# control_board_v006_Rev6.net
KiCad netlist of a schematic drawn in EAGLE
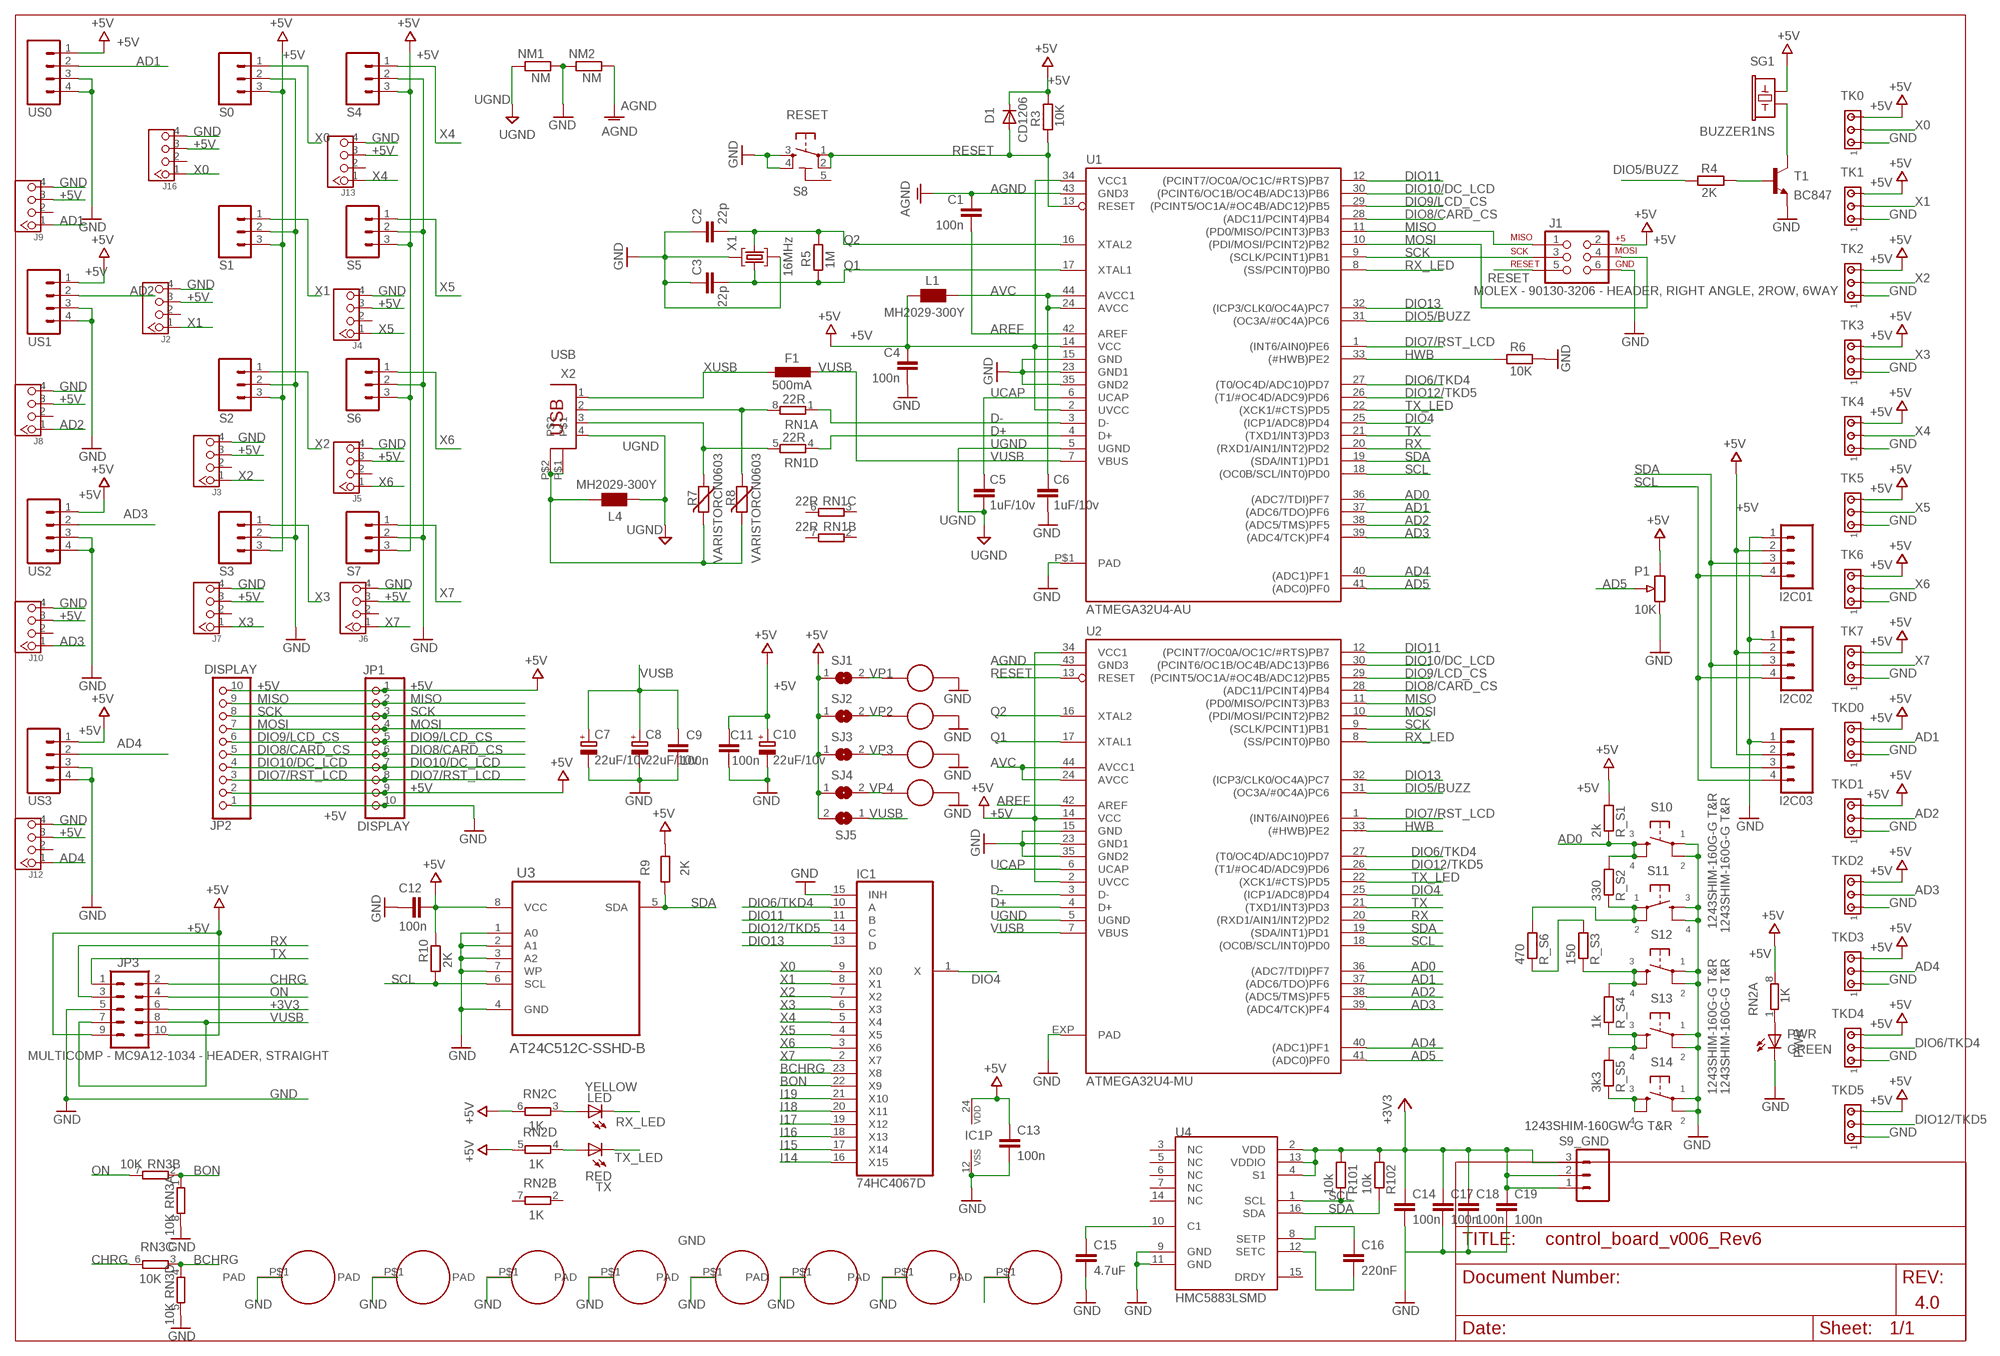
[diagram p0: schematic, sheet 1]

(export (version "E")
  (design (tool "Eeschema 10.0.6"))
  (components
    (comp (ref "C1")
      (value "100n")
      (footprint "eagle-import:C0603-ROUND")
      (libsource (lib "eagle-import") (part "C-EUC0603"))
    )
    (comp (ref "C2")
      (value "22p")
      (footprint "eagle-import:C0603-ROUND")
      (libsource (lib "eagle-import") (part "C-EUC0603"))
    )
    (comp (ref "C3")
      (value "22p")
      (footprint "eagle-import:C0603-ROUND")
      (libsource (lib "eagle-import") (part "C-EUC0603"))
    )
    (comp (ref "C4")
      (value "100n")
      (footprint "eagle-import:C0603-ROUND")
      (libsource (lib "eagle-import") (part "C-EUC0603"))
    )
    (comp (ref "C5")
      (value "1uF/10v")
      (footprint "eagle-import:C0603-ROUND")
      (libsource (lib "eagle-import") (part "C-EUC0603"))
    )
    (comp (ref "C6")
      (value "1uF/10v")
      (footprint "eagle-import:C0603-ROUND")
      (libsource (lib "eagle-import") (part "C-EUC0603"))
    )
    (comp (ref "C7")
      (value "22uF/10v")
      (footprint "eagle-import:SMC_B")
      (libsource (lib "eagle-import") (part "CPOL-EUSMCB"))
    )
    (comp (ref "C8")
      (value "22uF/10v")
      (footprint "eagle-import:SMC_B")
      (libsource (lib "eagle-import") (part "CPOL-EUSMCB"))
    )
    (comp (ref "C9")
      (value "100n")
      (footprint "eagle-import:C0603-ROUND")
      (libsource (lib "eagle-import") (part "C-EUC0603"))
    )
    (comp (ref "C10")
      (value "22uF/10v")
      (footprint "eagle-import:SMC_B")
      (libsource (lib "eagle-import") (part "CPOL-EUSMCB"))
    )
    (comp (ref "C11")
      (value "100n")
      (footprint "eagle-import:C0603-ROUND")
      (libsource (lib "eagle-import") (part "C-EUC0603"))
    )
    (comp (ref "C12")
      (value "100n")
      (footprint "eagle-import:C0603-ROUND")
      (libsource (lib "eagle-import") (part "C-EUC0603"))
    )
    (comp (ref "C13")
      (value "100n")
      (footprint "eagle-import:C0603-ROUND")
      (libsource (lib "eagle-import") (part "C-EUC0603"))
    )
    (comp (ref "C14")
      (value "100n")
      (footprint "eagle-import:C0603-ROUND")
      (libsource (lib "eagle-import") (part "C-EUC0603"))
    )
    (comp (ref "C15")
      (value "4.7uF")
      (footprint "eagle-import:C0603-ROUND")
      (libsource (lib "eagle-import") (part "C-EUC0603"))
    )
    (comp (ref "C16")
      (value "220nF")
      (footprint "eagle-import:C0603-ROUND")
      (libsource (lib "eagle-import") (part "C-EUC0603"))
    )
    (comp (ref "C17")
      (value "100n")
      (footprint "eagle-import:C0603-ROUND")
      (libsource (lib "eagle-import") (part "C-EUC0603"))
    )
    (comp (ref "C18")
      (value "100n")
      (footprint "eagle-import:C0603-ROUND")
      (libsource (lib "eagle-import") (part "C-EUC0603"))
    )
    (comp (ref "C19")
      (value "100n")
      (footprint "eagle-import:C0603-ROUND")
      (libsource (lib "eagle-import") (part "C-EUC0603"))
    )
    (comp (ref "D1")
      (value "CD1206")
      (footprint "eagle-import:MINIMELF")
      (libsource (lib "eagle-import") (part "DIODE-MINIMELF"))
    )
    (comp (ref "F1")
      (value "500mA")
      (footprint "eagle-import:L1812")
      (libsource (lib "eagle-import") (part "L-EUL1812"))
    )
    (comp (ref "H1")
      (value "2.5-MOUNTING-HOLE")
      (footprint "eagle-import:2.5PAD")
      (libsource (lib "eagle-import") (part "2.5-MOUNTING-HOLE"))
    )
    (comp (ref "H2")
      (value "2.5-MOUNTING-HOLE")
      (footprint "eagle-import:2.5PAD")
      (libsource (lib "eagle-import") (part "2.5-MOUNTING-HOLE"))
    )
    (comp (ref "H3")
      (value "2.5-MOUNTING-HOLE")
      (footprint "eagle-import:2.5PAD")
      (libsource (lib "eagle-import") (part "2.5-MOUNTING-HOLE"))
    )
    (comp (ref "H4")
      (value "2.5-MOUNTING-HOLE")
      (footprint "eagle-import:2.5PAD")
      (libsource (lib "eagle-import") (part "2.5-MOUNTING-HOLE"))
    )
    (comp (ref "H5")
      (value "2.5-MOUNTING-HOLE")
      (footprint "eagle-import:2.5PAD")
      (libsource (lib "eagle-import") (part "2.5-MOUNTING-HOLE"))
    )
    (comp (ref "H6")
      (value "2.5-MOUNTING-HOLE")
      (footprint "eagle-import:2.5PAD")
      (libsource (lib "eagle-import") (part "2.5-MOUNTING-HOLE"))
    )
    (comp (ref "H7")
      (value "2.5-MOUNTING-HOLE")
      (footprint "eagle-import:2.5PAD")
      (libsource (lib "eagle-import") (part "2.5-MOUNTING-HOLE"))
    )
    (comp (ref "H8")
      (value "2.5-MOUNTING-HOLE")
      (footprint "eagle-import:2.5PAD")
      (libsource (lib "eagle-import") (part "2.5-MOUNTING-HOLE"))
    )
    (comp (ref "I2C01")
      (value "M04PTH")
      (footprint "eagle-import:1X04")
      (libsource (lib "eagle-import") (part "M04PTH"))
    )
    (comp (ref "I2C02")
      (value "M04PTH")
      (footprint "eagle-import:1X04")
      (libsource (lib "eagle-import") (part "M04PTH"))
    )
    (comp (ref "I2C03")
      (value "M04PTH")
      (footprint "eagle-import:1X04")
      (libsource (lib "eagle-import") (part "M04PTH"))
    )
    (comp (ref "IC1")
      (value "74HC4067D")
      (footprint "eagle-import:SO24W")
      (libsource (lib "eagle-import") (part "4067D"))
    )
    (comp (ref "J1")
      (value "MOLEX - 90130-3206 - HEADER, RIGHT ANGLE, 2ROW, 6WAY")
      (footprint "eagle-import:2X3")
      (libsource (lib "eagle-import") (part "AVR_SPI_PRG_6PTH"))
    )
    (comp (ref "J2")
      (value "TWIG-4P-2.0-2.0")
      (footprint "eagle-import:4P-2.0")
      (libsource (lib "eagle-import") (part "TWIG-4P-2.0-2.0"))
    )
    (comp (ref "J3")
      (value "TWIG-4P-2.0-2.0")
      (footprint "eagle-import:4P-2.0")
      (libsource (lib "eagle-import") (part "TWIG-4P-2.0-2.0"))
    )
    (comp (ref "J4")
      (value "TWIG-4P-2.0-2.0")
      (footprint "eagle-import:4P-2.0")
      (libsource (lib "eagle-import") (part "TWIG-4P-2.0-2.0"))
    )
    (comp (ref "J5")
      (value "TWIG-4P-2.0-2.0")
      (footprint "eagle-import:4P-2.0")
      (libsource (lib "eagle-import") (part "TWIG-4P-2.0-2.0"))
    )
    (comp (ref "J6")
      (value "TWIG-4P-2.0-2.0")
      (footprint "eagle-import:4P-2.0")
      (libsource (lib "eagle-import") (part "TWIG-4P-2.0-2.0"))
    )
    (comp (ref "J7")
      (value "TWIG-4P-2.0-2.0")
      (footprint "eagle-import:4P-2.0")
      (libsource (lib "eagle-import") (part "TWIG-4P-2.0-2.0"))
    )
    (comp (ref "J8")
      (value "TWIG-4P-2.0-2.0")
      (footprint "eagle-import:4P-2.0")
      (libsource (lib "eagle-import") (part "TWIG-4P-2.0-2.0"))
    )
    (comp (ref "J9")
      (value "TWIG-4P-2.0-2.0")
      (footprint "eagle-import:4P-2.0")
      (libsource (lib "eagle-import") (part "TWIG-4P-2.0-2.0"))
    )
    (comp (ref "J10")
      (value "TWIG-4P-2.0-2.0")
      (footprint "eagle-import:4P-2.0")
      (libsource (lib "eagle-import") (part "TWIG-4P-2.0-2.0"))
    )
    (comp (ref "J12")
      (value "TWIG-4P-2.0-2.0")
      (footprint "eagle-import:4P-2.0")
      (libsource (lib "eagle-import") (part "TWIG-4P-2.0-2.0"))
    )
    (comp (ref "J13")
      (value "TWIG-4P-2.0-2.0")
      (footprint "eagle-import:4P-2.0")
      (libsource (lib "eagle-import") (part "TWIG-4P-2.0-2.0"))
    )
    (comp (ref "J16")
      (value "TWIG-4P-2.0-2.0")
      (footprint "eagle-import:4P-2.0")
      (libsource (lib "eagle-import") (part "TWIG-4P-2.0-2.0"))
    )
    (comp (ref "JP1")
      (value "DISPLAY")
      (footprint "eagle-import:1X10-TH")
      (libsource (lib "eagle-import") (part "PINHD-1X10TH"))
    )
    (comp (ref "JP2")
      (value "DISPLAY")
      (footprint "eagle-import:1X10-TH")
      (libsource (lib "eagle-import") (part "PINHD-1X10TH"))
    )
    (comp (ref "JP3")
      (value "MULTICOMP - MC9A12-1034 - HEADER, STRAIGHT")
      (footprint "eagle-import:2X5-SHROUDED_LOCK")
      (libsource (lib "eagle-import") (part "M05X2SHD_LOCK"))
    )
    (comp (ref "L1")
      (value "MH2029-300Y")
      (footprint "eagle-import:0805")
      (libsource (lib "eagle-import") (part "WE-CBF_0805"))
    )
    (comp (ref "L4")
      (value "MH2029-300Y")
      (footprint "eagle-import:0805")
      (libsource (lib "eagle-import") (part "WE-CBF_0805"))
    )
    (comp (ref "LED")
      (value "YELLOW")
      (footprint "eagle-import:CHIP-LED0805")
      (libsource (lib "eagle-import") (part "LEDCHIP-LED0805"))
    )
    (comp (ref "NM1")
      (value "NM")
      (footprint "eagle-import:R0805")
      (libsource (lib "eagle-import") (part "resistor_R-EU_R0805"))
    )
    (comp (ref "NM2")
      (value "NM")
      (footprint "eagle-import:R0805")
      (libsource (lib "eagle-import") (part "resistor_R-EU_R0805"))
    )
    (comp (ref "P1")
      (value "10K")
      (footprint "eagle-import:POT-V")
      (libsource (lib "eagle-import") (part "POT-VERTICAL"))
    )
    (comp (ref "PTZ1")
      (value "LOTTIE_LEMON_PADS_SUP")
      (footprint "eagle-import:PADS_LOTTIE_LEMON_SUP")
      (libsource (lib "eagle-import") (part "LOTTIE_LEMON_PADS_SUP"))
    )
    (comp (ref "PTZ2")
      (value "LOTTIE_LEMON_PADS_SUP")
      (footprint "eagle-import:PADS_LOTTIE_LEMON_SUP")
      (libsource (lib "eagle-import") (part "LOTTIE_LEMON_PADS_SUP"))
    )
    (comp (ref "PTZ3")
      (value "LOTTIE_LEMON_PADS_SUP1")
      (footprint "eagle-import:PADS_LOTTIE_LEMON_SUP")
      (libsource (lib "eagle-import") (part "LOTTIE_LEMON_PADS_SUP1"))
    )
    (comp (ref "PTZ4")
      (value "LOTTIE_LEMON_PADS_SUP1")
      (footprint "eagle-import:PADS_LOTTIE_LEMON_SUP")
      (libsource (lib "eagle-import") (part "LOTTIE_LEMON_PADS_SUP1"))
    )
    (comp (ref "PWR")
      (value "PWR")
      (footprint "eagle-import:CHIP-LED0805")
      (libsource (lib "eagle-import") (part "LEDCHIP-LED0805"))
    )
    (comp (ref "R3")
      (value "10K")
      (footprint "eagle-import:R0603-ROUND")
      (libsource (lib "eagle-import") (part "R-EU_R0603"))
    )
    (comp (ref "R4")
      (value "2K")
      (footprint "eagle-import:R0603-ROUND")
      (libsource (lib "eagle-import") (part "R-EU_R0603"))
    )
    (comp (ref "R5")
      (value "1M")
      (footprint "eagle-import:R0603-ROUND")
      (libsource (lib "eagle-import") (part "R-EU_R0603"))
    )
    (comp (ref "R6")
      (value "10K")
      (footprint "eagle-import:R0603-ROUND")
      (libsource (lib "eagle-import") (part "R-EU_R0603"))
    )
    (comp (ref "R7")
      (value "VARISTORCN0603")
      (footprint "eagle-import:CT_CN0603")
      (libsource (lib "eagle-import") (part "VARISTORCN0603"))
    )
    (comp (ref "R8")
      (value "VARISTORCN0603")
      (footprint "eagle-import:CT_CN0603")
      (libsource (lib "eagle-import") (part "VARISTORCN0603"))
    )
    (comp (ref "R9")
      (value "2K")
      (footprint "eagle-import:R0603-ROUND")
      (libsource (lib "eagle-import") (part "R-EU_R0603"))
    )
    (comp (ref "R10")
      (value "2K")
      (footprint "eagle-import:R0603-ROUND")
      (libsource (lib "eagle-import") (part "R-EU_R0603"))
    )
    (comp (ref "R101")
      (value "10k")
      (footprint "eagle-import:R0603-ROUND")
      (libsource (lib "eagle-import") (part "R-EU_R0603"))
    )
    (comp (ref "R102")
      (value "10k")
      (footprint "eagle-import:R0603-ROUND")
      (libsource (lib "eagle-import") (part "R-EU_R0603"))
    )
    (comp (ref "RN1")
      (value "22R")
      (footprint "eagle-import:CAY16")
      (fields (field (name "OC_FARNELL") "unknown") (field (name "OC_NEWARK") "unknown"))
      (libsource (lib "eagle-import") (part "4R-NCAY16"))
    )
    (comp (ref "RN2")
      (value "1K")
      (footprint "eagle-import:CAY16")
      (libsource (lib "eagle-import") (part "4R-NCAY16"))
    )
    (comp (ref "RN3")
      (value "10K")
      (footprint "eagle-import:CAY16")
      (fields (field (name "OC_FARNELL") "unknown") (field (name "OC_NEWARK") "unknown"))
      (libsource (lib "eagle-import") (part "4R-NCAY16"))
    )
    (comp (ref "R_S1")
      (value "2k")
      (footprint "eagle-import:R0603-ROUND")
      (libsource (lib "eagle-import") (part "R-EU_R0603"))
    )
    (comp (ref "R_S2")
      (value "330")
      (footprint "eagle-import:R0603-ROUND")
      (libsource (lib "eagle-import") (part "R-EU_R0603"))
    )
    (comp (ref "R_S3")
      (value "150")
      (footprint "eagle-import:R0603-ROUND")
      (libsource (lib "eagle-import") (part "R-EU_R0603"))
    )
    (comp (ref "R_S4")
      (value "1k")
      (footprint "eagle-import:R0603-ROUND")
      (libsource (lib "eagle-import") (part "R-EU_R0603"))
    )
    (comp (ref "R_S5")
      (value "3k3")
      (footprint "eagle-import:R0603-ROUND")
      (libsource (lib "eagle-import") (part "R-EU_R0603"))
    )
    (comp (ref "R_S6")
      (value "470")
      (footprint "eagle-import:R0603-ROUND")
      (libsource (lib "eagle-import") (part "R-EU_R0603"))
    )
    (comp (ref "S0")
      (value "M03PTH")
      (footprint "eagle-import:1X03")
      (libsource (lib "eagle-import") (part "M03PTH"))
    )
    (comp (ref "S1")
      (value "M03PTH")
      (footprint "eagle-import:1X03")
      (libsource (lib "eagle-import") (part "M03PTH"))
    )
    (comp (ref "S2")
      (value "M03PTH")
      (footprint "eagle-import:1X03")
      (libsource (lib "eagle-import") (part "M03PTH"))
    )
    (comp (ref "S3")
      (value "M03PTH")
      (footprint "eagle-import:1X03")
      (libsource (lib "eagle-import") (part "M03PTH"))
    )
    (comp (ref "S4")
      (value "M03PTH")
      (footprint "eagle-import:1X03")
      (libsource (lib "eagle-import") (part "M03PTH"))
    )
    (comp (ref "S5")
      (value "M03PTH")
      (footprint "eagle-import:1X03")
      (libsource (lib "eagle-import") (part "M03PTH"))
    )
    (comp (ref "S6")
      (value "M03PTH")
      (footprint "eagle-import:1X03")
      (libsource (lib "eagle-import") (part "M03PTH"))
    )
    (comp (ref "S7")
      (value "M03PTH")
      (footprint "eagle-import:1X03")
      (libsource (lib "eagle-import") (part "M03PTH"))
    )
    (comp (ref "S8")
      (value "RESET")
      (footprint "eagle-import:TS42")
      (libsource (lib "eagle-import") (part "TS42"))
    )
    (comp (ref "S9_GND")
      (value "M03PTH")
      (footprint "eagle-import:1X03")
      (libsource (lib "eagle-import") (part "M03PTH"))
    )
    (comp (ref "S10")
      (value "1243SHIM-160G-G T&R")
      (footprint "eagle-import:TACTILE-SMD-12MM")
      (libsource (lib "eagle-import") (part "TACTILE_SWITCHTACTILE_SWITCH_SMD-12MM"))
    )
    (comp (ref "S11")
      (value "1243SHIM-160G-G T&R")
      (footprint "eagle-import:TACTILE-SMD-12MM")
      (libsource (lib "eagle-import") (part "TACTILE_SWITCHTACTILE_SWITCH_SMD-12MM"))
    )
    (comp (ref "S12")
      (value "1243SHIM-160G-G T&R")
      (footprint "eagle-import:TACTILE-SMD-12MM")
      (libsource (lib "eagle-import") (part "TACTILE_SWITCHTACTILE_SWITCH_SMD-12MM"))
    )
    (comp (ref "S13")
      (value "1243SHIM-160G-G T&R")
      (footprint "eagle-import:TACTILE-SMD-12MM")
      (libsource (lib "eagle-import") (part "TACTILE_SWITCHTACTILE_SWITCH_SMD-12MM"))
    )
    (comp (ref "S14")
      (value "1243SHIM-160GW-G T&R")
      (footprint "eagle-import:TACTILE-SMD-12MM")
      (libsource (lib "eagle-import") (part "TACTILE_SWITCHTACTILE_SWITCH_SMD-12MM"))
    )
    (comp (ref "SG1")
      (value "BUZZER1NS")
      (footprint "eagle-import:BUZZER-12MM-NS")
      (libsource (lib "eagle-import") (part "BUZZER1NS"))
    )
    (comp (ref "SJ1") (value "SJ") (footprint "eagle-import:SJ") (libsource (lib "eagle-import") (part "SJ")))
    (comp (ref "SJ2") (value "SJ") (footprint "eagle-import:SJ") (libsource (lib "eagle-import") (part "SJ")))
    (comp (ref "SJ3") (value "SJ") (footprint "eagle-import:SJ") (libsource (lib "eagle-import") (part "SJ")))
    (comp (ref "SJ4") (value "SJ") (footprint "eagle-import:SJ") (libsource (lib "eagle-import") (part "SJ")))
    (comp (ref "SJ5")
      (value "SJL")
      (footprint "eagle-import:SJL")
      (libsource (lib "eagle-import") (part "SJL"))
    )
    (comp (ref "T1")
      (value "BC847")
      (footprint "eagle-import:SOT23")
      (libsource (lib "eagle-import") (part "BC847"))
    )
    (comp (ref "TK0")
      (value "MTA03-100")
      (footprint "eagle-import:10X03MTA")
      (libsource (lib "eagle-import") (part "MTA03-100"))
    )
    (comp (ref "TK1")
      (value "MTA03-100")
      (footprint "eagle-import:10X03MTA")
      (libsource (lib "eagle-import") (part "MTA03-100"))
    )
    (comp (ref "TK2")
      (value "MTA03-100")
      (footprint "eagle-import:10X03MTA")
      (libsource (lib "eagle-import") (part "MTA03-100"))
    )
    (comp (ref "TK3")
      (value "MTA03-100")
      (footprint "eagle-import:10X03MTA")
      (libsource (lib "eagle-import") (part "MTA03-100"))
    )
    (comp (ref "TK4")
      (value "MTA03-100")
      (footprint "eagle-import:10X03MTA")
      (libsource (lib "eagle-import") (part "MTA03-100"))
    )
    (comp (ref "TK5")
      (value "MTA03-100")
      (footprint "eagle-import:10X03MTA")
      (libsource (lib "eagle-import") (part "MTA03-100"))
    )
    (comp (ref "TK6")
      (value "MTA03-100")
      (footprint "eagle-import:10X03MTA")
      (libsource (lib "eagle-import") (part "MTA03-100"))
    )
    (comp (ref "TK7")
      (value "MTA03-100")
      (footprint "eagle-import:10X03MTA")
      (libsource (lib "eagle-import") (part "MTA03-100"))
    )
    (comp (ref "TKD0")
      (value "MTA03-100")
      (footprint "eagle-import:10X03MTA")
      (libsource (lib "eagle-import") (part "MTA03-100"))
    )
    (comp (ref "TKD1")
      (value "MTA03-100")
      (footprint "eagle-import:10X03MTA")
      (libsource (lib "eagle-import") (part "MTA03-100"))
    )
    (comp (ref "TKD2")
      (value "MTA03-100")
      (footprint "eagle-import:10X03MTA")
      (libsource (lib "eagle-import") (part "MTA03-100"))
    )
    (comp (ref "TKD3")
      (value "MTA03-100")
      (footprint "eagle-import:10X03MTA")
      (libsource (lib "eagle-import") (part "MTA03-100"))
    )
    (comp (ref "TKD4")
      (value "MTA03-100")
      (footprint "eagle-import:10X03MTA")
      (libsource (lib "eagle-import") (part "MTA03-100"))
    )
    (comp (ref "TKD5")
      (value "MTA03-100")
      (footprint "eagle-import:10X03MTA")
      (libsource (lib "eagle-import") (part "MTA03-100"))
    )
    (comp (ref "TX")
      (value "RED")
      (footprint "eagle-import:CHIP-LED0805")
      (libsource (lib "eagle-import") (part "LEDCHIP-LED0805"))
    )
    (comp (ref "U$2")
      (value "COMPLUBOT_LOTTIE_LEMON_BASE_TYPE002")
      (footprint "eagle-import:COMPLUBOT_BASE_ROBOT_002")
      (libsource (lib "eagle-import") (part "COMPLUBOT_LOTTIE_LEMON_BASE_TYPE002"))
    )
    (comp (ref "U1")
      (value "ATMEGA32U4-AU")
      (footprint "eagle-import:TQFP44-PAD")
      (libsource (lib "eagle-import") (part "ATMEGA32U4-XUAU"))
    )
    (comp (ref "U2")
      (value "ATMEGA32U4-MU")
      (footprint "eagle-import:QFN44ML7X7")
      (libsource (lib "eagle-import") (part "ATMEGA32U4-XUMU"))
    )
    (comp (ref "U3")
      (value "AT24C512C-SSHD-B")
      (footprint "eagle-import:SOIC127P600X175-8N")
      (fields (field (name "MPN") "AT24C128BN-SH-B"))
      (libsource (lib "eagle-import") (part "AT24C128BN-SH-B"))
    )
    (comp (ref "U4")
      (value "HMC5883LSMD")
      (footprint "eagle-import:16LPCC")
      (libsource (lib "eagle-import") (part "HMC5883LSMD"))
    )
    (comp (ref "US0")
      (value "M04PTH")
      (footprint "eagle-import:1X04")
      (libsource (lib "eagle-import") (part "M04PTH"))
    )
    (comp (ref "US1")
      (value "M04PTH")
      (footprint "eagle-import:1X04")
      (libsource (lib "eagle-import") (part "M04PTH"))
    )
    (comp (ref "US2")
      (value "M04PTH")
      (footprint "eagle-import:1X04")
      (libsource (lib "eagle-import") (part "M04PTH"))
    )
    (comp (ref "US3")
      (value "M04PTH")
      (footprint "eagle-import:1X04")
      (libsource (lib "eagle-import") (part "M04PTH"))
    )
    (comp (ref "X1")
      (value "16MHz")
      (footprint "eagle-import:CRYSTAL-3.2-2.5")
      (libsource (lib "eagle-import") (part "CRYSTAL-3.2-2.5"))
    )
    (comp (ref "X2")
      (value "USB")
      (footprint "eagle-import:PN61729")
      (libsource (lib "eagle-import") (part "PN61729"))
    )
  )
  (nets
    (net (code "1") (name "+3V3") (class "Default")
      (node (ref "C14") (pin "1") (pinfunction "1_1") (pintype "passive"))
      (node (ref "C17") (pin "1") (pinfunction "1_1") (pintype "passive"))
      (node (ref "C18") (pin "1") (pinfunction "1_1") (pintype "passive"))
      (node (ref "C19") (pin "1") (pinfunction "1_1") (pintype "passive"))
      (node (ref "JP3") (pin "6") (pinfunction "6_6") (pintype "passive"))
      (node (ref "R101") (pin "2") (pinfunction "2_2") (pintype "passive"))
      (node (ref "R102") (pin "2") (pinfunction "2_2") (pintype "passive"))
      (node (ref "S9_GND") (pin "1") (pinfunction "1_1") (pintype "passive"))
      (node (ref "S9_GND") (pin "2") (pinfunction "2_2") (pintype "passive"))
      (node (ref "S9_GND") (pin "3") (pinfunction "3_3") (pintype "passive"))
      (node (ref "U4") (pin "13") (pinfunction "VDDIO_13") (pintype "bidirectional"))
      (node (ref "U4") (pin "2") (pinfunction "VDD_2") (pintype "bidirectional"))
      (node (ref "U4") (pin "4") (pinfunction "S1_4") (pintype "bidirectional"))
    )
    (net (code "2") (name "+5V") (class "Default")
      (node (ref "C10") (pin "+") (pinfunction "+_+") (pintype "passive"))
      (node (ref "C11") (pin "1") (pinfunction "1_1") (pintype "passive"))
      (node (ref "C12") (pin "1") (pinfunction "1_1") (pintype "passive"))
      (node (ref "C13") (pin "1") (pinfunction "1_1") (pintype "passive"))
      (node (ref "C4") (pin "1") (pinfunction "1_1") (pintype "passive"))
      (node (ref "D1") (pin "C") (pinfunction "C_C") (pintype "passive"))
      (node (ref "I2C01") (pin "2") (pinfunction "2_2") (pintype "passive"))
      (node (ref "I2C02") (pin "2") (pinfunction "2_2") (pintype "passive"))
      (node (ref "I2C03") (pin "2") (pinfunction "2_2") (pintype "passive"))
      (node (ref "IC1") (pin "24") (pinfunction "VDD_24") (pintype "power_in"))
      (node (ref "J1") (pin "2") (pinfunction "2_2") (pintype "passive"))
      (node (ref "J10") (pin "3") (pinfunction "3_3") (pintype "bidirectional"))
      (node (ref "J12") (pin "3") (pinfunction "3_3") (pintype "bidirectional"))
      (node (ref "J13") (pin "3") (pinfunction "3_3") (pintype "bidirectional"))
      (node (ref "J16") (pin "3") (pinfunction "3_3") (pintype "bidirectional"))
      (node (ref "J2") (pin "3") (pinfunction "3_3") (pintype "bidirectional"))
      (node (ref "J3") (pin "3") (pinfunction "3_3") (pintype "bidirectional"))
      (node (ref "J4") (pin "3") (pinfunction "3_3") (pintype "bidirectional"))
      (node (ref "J5") (pin "3") (pinfunction "3_3") (pintype "bidirectional"))
      (node (ref "J6") (pin "3") (pinfunction "3_3") (pintype "bidirectional"))
      (node (ref "J7") (pin "3") (pinfunction "3_3") (pintype "bidirectional"))
      (node (ref "J8") (pin "3") (pinfunction "3_3") (pintype "bidirectional"))
      (node (ref "J9") (pin "3") (pinfunction "3_3") (pintype "bidirectional"))
      (node (ref "JP1") (pin "1") (pinfunction "1_1") (pintype "passive"))
      (node (ref "JP1") (pin "9") (pinfunction "9_9") (pintype "passive"))
      (node (ref "JP2") (pin "10") (pinfunction "10_10") (pintype "passive"))
      (node (ref "JP2") (pin "2") (pinfunction "2_2") (pintype "passive"))
      (node (ref "JP3") (pin "10") (pinfunction "10_10") (pintype "passive"))
      (node (ref "JP3") (pin "9") (pinfunction "9_9") (pintype "passive"))
      (node (ref "L1") (pin "2") (pinfunction "2_2") (pintype "passive"))
      (node (ref "P1") (pin "B") (pinfunction "B_B") (pintype "passive"))
      (node (ref "R10") (pin "1") (pinfunction "1_1") (pintype "passive"))
      (node (ref "R3") (pin "1") (pinfunction "1_1") (pintype "passive"))
      (node (ref "R9") (pin "2") (pinfunction "2_2") (pintype "passive"))
      (node (ref "RN2") (pin "5") (pinfunction "2_5") (pintype "passive"))
      (node (ref "RN2") (pin "6") (pinfunction "2_6") (pintype "passive"))
      (node (ref "RN2") (pin "8") (pinfunction "2_8") (pintype "passive"))
      (node (ref "R_S1") (pin "2") (pinfunction "2_2") (pintype "passive"))
      (node (ref "S0") (pin "3") (pinfunction "3_3") (pintype "passive"))
      (node (ref "S1") (pin "3") (pinfunction "3_3") (pintype "passive"))
      (node (ref "S2") (pin "3") (pinfunction "3_3") (pintype "passive"))
      (node (ref "S3") (pin "3") (pinfunction "3_3") (pintype "passive"))
      (node (ref "S4") (pin "3") (pinfunction "3_3") (pintype "passive"))
      (node (ref "S5") (pin "3") (pinfunction "3_3") (pintype "passive"))
      (node (ref "S6") (pin "3") (pinfunction "3_3") (pintype "passive"))
      (node (ref "S7") (pin "3") (pinfunction "3_3") (pintype "passive"))
      (node (ref "SG1") (pin "+") (pinfunction "1_+") (pintype "passive"))
      (node (ref "SJ1") (pin "1") (pinfunction "1_1") (pintype "passive"))
      (node (ref "SJ2") (pin "1") (pinfunction "1_1") (pintype "passive"))
      (node (ref "SJ3") (pin "1") (pinfunction "1_1") (pintype "passive"))
      (node (ref "SJ4") (pin "1") (pinfunction "1_1") (pintype "passive"))
      (node (ref "SJ5") (pin "2") (pinfunction "2_2") (pintype "passive"))
      (node (ref "TK0") (pin "3") (pinfunction "3_3") (pintype "passive"))
      (node (ref "TK1") (pin "3") (pinfunction "3_3") (pintype "passive"))
      (node (ref "TK2") (pin "3") (pinfunction "3_3") (pintype "passive"))
      (node (ref "TK3") (pin "3") (pinfunction "3_3") (pintype "passive"))
      (node (ref "TK4") (pin "3") (pinfunction "3_3") (pintype "passive"))
      (node (ref "TK5") (pin "3") (pinfunction "3_3") (pintype "passive"))
      (node (ref "TK6") (pin "3") (pinfunction "3_3") (pintype "passive"))
      (node (ref "TK7") (pin "3") (pinfunction "3_3") (pintype "passive"))
      (node (ref "TKD0") (pin "3") (pinfunction "3_3") (pintype "passive"))
      (node (ref "TKD1") (pin "3") (pinfunction "3_3") (pintype "passive"))
      (node (ref "TKD2") (pin "3") (pinfunction "3_3") (pintype "passive"))
      (node (ref "TKD3") (pin "3") (pinfunction "3_3") (pintype "passive"))
      (node (ref "TKD4") (pin "3") (pinfunction "3_3") (pintype "passive"))
      (node (ref "TKD5") (pin "3") (pinfunction "3_3") (pintype "passive"))
      (node (ref "U1") (pin "14") (pinfunction "VCC_14") (pintype "power_in"))
      (node (ref "U1") (pin "2") (pinfunction "UVCC_2") (pintype "power_in"))
      (node (ref "U1") (pin "34") (pinfunction "VCC1_34") (pintype "power_in"))
      (node (ref "U2") (pin "14") (pinfunction "VCC_14") (pintype "power_in"))
      (node (ref "U2") (pin "2") (pinfunction "UVCC_2") (pintype "power_in"))
      (node (ref "U2") (pin "34") (pinfunction "VCC1_34") (pintype "power_in"))
      (node (ref "U3") (pin "8") (pinfunction "VCC_8") (pintype "power_in"))
      (node (ref "US0") (pin "1") (pinfunction "1_1") (pintype "passive"))
      (node (ref "US1") (pin "1") (pinfunction "1_1") (pintype "passive"))
      (node (ref "US2") (pin "1") (pinfunction "1_1") (pintype "passive"))
      (node (ref "US3") (pin "1") (pinfunction "1_1") (pintype "passive"))
    )
    (net (code "3") (name "/5-GND") (class "Default")
      (node (ref "S8") (pin "5") (pinfunction "5-GND_5") (pintype "power_in"))
    )
    (net (code "4") (name "/AD0") (class "Default")
      (node (ref "R_S1") (pin "1") (pinfunction "1_1") (pintype "passive"))
      (node (ref "R_S2") (pin "2") (pinfunction "2_2") (pintype "passive"))
      (node (ref "S10") (pin "P$3") (pinfunction "3_P$3") (pintype "passive"))
      (node (ref "S10") (pin "P$4") (pinfunction "4_P$4") (pintype "passive"))
      (node (ref "U1") (pin "36") (pinfunction "(ADC7/TDI)PF7_36") (pintype "bidirectional"))
      (node (ref "U2") (pin "36") (pinfunction "(ADC7/TDI)PF7_36") (pintype "bidirectional"))
    )
    (net (code "5") (name "/AD1") (class "Default")
      (node (ref "J9") (pin "1") (pinfunction "1_1") (pintype "bidirectional"))
      (node (ref "TKD0") (pin "2") (pinfunction "2_2") (pintype "passive"))
      (node (ref "U1") (pin "37") (pinfunction "(ADC6/TDO)PF6_37") (pintype "bidirectional"))
      (node (ref "U2") (pin "37") (pinfunction "(ADC6/TDO)PF6_37") (pintype "bidirectional"))
      (node (ref "US0") (pin "2") (pinfunction "2_2") (pintype "passive"))
    )
    (net (code "6") (name "/AD2") (class "Default")
      (node (ref "J8") (pin "1") (pinfunction "1_1") (pintype "bidirectional"))
      (node (ref "TKD1") (pin "2") (pinfunction "2_2") (pintype "passive"))
      (node (ref "U1") (pin "38") (pinfunction "(ADC5/TMS)PF5_38") (pintype "bidirectional"))
      (node (ref "U2") (pin "38") (pinfunction "(ADC5/TMS)PF5_38") (pintype "bidirectional"))
      (node (ref "US1") (pin "2") (pinfunction "2_2") (pintype "passive"))
    )
    (net (code "7") (name "/AD3") (class "Default")
      (node (ref "J10") (pin "1") (pinfunction "1_1") (pintype "bidirectional"))
      (node (ref "TKD2") (pin "2") (pinfunction "2_2") (pintype "passive"))
      (node (ref "U1") (pin "39") (pinfunction "(ADC4/TCK)PF4_39") (pintype "bidirectional"))
      (node (ref "U2") (pin "39") (pinfunction "(ADC4/TCK)PF4_39") (pintype "bidirectional"))
      (node (ref "US2") (pin "2") (pinfunction "2_2") (pintype "passive"))
    )
    (net (code "8") (name "/AD4") (class "Default")
      (node (ref "J12") (pin "1") (pinfunction "1_1") (pintype "bidirectional"))
      (node (ref "TKD3") (pin "2") (pinfunction "2_2") (pintype "passive"))
      (node (ref "U1") (pin "40") (pinfunction "(ADC1)PF1_40") (pintype "bidirectional"))
      (node (ref "U2") (pin "40") (pinfunction "(ADC1)PF1_40") (pintype "bidirectional"))
      (node (ref "US3") (pin "2") (pinfunction "2_2") (pintype "passive"))
    )
    (net (code "9") (name "/AD5") (class "Default")
      (node (ref "P1") (pin "C") (pinfunction "C_C") (pintype "passive"))
      (node (ref "U1") (pin "41") (pinfunction "(ADC0)PF0_41") (pintype "bidirectional"))
      (node (ref "U2") (pin "41") (pinfunction "(ADC0)PF0_41") (pintype "bidirectional"))
    )
    (net (code "10") (name "/AREF") (class "Default")
      (node (ref "C1") (pin "2") (pinfunction "2_2") (pintype "passive"))
      (node (ref "U1") (pin "42") (pinfunction "AREF_42") (pintype "power_in"))
      (node (ref "U2") (pin "42") (pinfunction "AREF_42") (pintype "power_in"))
    )
    (net (code "11") (name "/AVC") (class "Default")
      (node (ref "C6") (pin "1") (pinfunction "1_1") (pintype "passive"))
      (node (ref "L1") (pin "1") (pinfunction "1_1") (pintype "passive"))
      (node (ref "U1") (pin "24") (pinfunction "AVCC_24") (pintype "power_in"))
      (node (ref "U1") (pin "44") (pinfunction "AVCC1_44") (pintype "power_in"))
      (node (ref "U2") (pin "24") (pinfunction "AVCC_24") (pintype "power_in"))
      (node (ref "U2") (pin "44") (pinfunction "AVCC1_44") (pintype "power_in"))
    )
    (net (code "12") (name "/BCHRG") (class "Default")
      (node (ref "IC1") (pin "23") (pinfunction "X8_23") (pintype "input"))
      (node (ref "RN3") (pin "3") (pinfunction "1_3") (pintype "passive"))
      (node (ref "RN3") (pin "4") (pinfunction "1_4") (pintype "passive"))
    )
    (net (code "13") (name "/BON") (class "Default")
      (node (ref "IC1") (pin "22") (pinfunction "X9_22") (pintype "input"))
      (node (ref "RN3") (pin "1") (pinfunction "1_1") (pintype "passive"))
      (node (ref "RN3") (pin "2") (pinfunction "1_2") (pintype "passive"))
    )
    (net (code "14") (name "/CHRG") (class "Default")
      (node (ref "JP3") (pin "2") (pinfunction "2_2") (pintype "passive"))
      (node (ref "RN3") (pin "6") (pinfunction "2_6") (pintype "passive"))
    )
    (net (code "15") (name "/D+") (class "Default")
      (node (ref "RN1") (pin "4") (pinfunction "1_4") (pintype "passive"))
      (node (ref "U1") (pin "4") (pinfunction "D+_4") (pintype "bidirectional"))
      (node (ref "U2") (pin "4") (pinfunction "D+_4") (pintype "bidirectional"))
    )
    (net (code "16") (name "/D-") (class "Default")
      (node (ref "RN1") (pin "1") (pinfunction "1_1") (pintype "passive"))
      (node (ref "U1") (pin "3") (pinfunction "D-_3") (pintype "bidirectional"))
      (node (ref "U2") (pin "3") (pinfunction "D-_3") (pintype "bidirectional"))
    )
    (net (code "17") (name "/DIO4") (class "Default")
      (node (ref "IC1") (pin "1") (pinfunction "X_1") (pintype "output"))
      (node (ref "U1") (pin "25") (pinfunction "(ICP1/ADC8)PD4_25") (pintype "bidirectional"))
      (node (ref "U2") (pin "25") (pinfunction "(ICP1/ADC8)PD4_25") (pintype "bidirectional"))
    )
    (net (code "18") (name "/DIO5{slash}BUZZ") (class "Default")
      (node (ref "R4") (pin "2") (pinfunction "2_2") (pintype "passive"))
      (node (ref "U1") (pin "31") (pinfunction "(OC3A/#0C4A)PC6_31") (pintype "bidirectional"))
      (node (ref "U2") (pin "31") (pinfunction "(OC3A/#0C4A)PC6_31") (pintype "bidirectional"))
    )
    (net (code "19") (name "/DIO6{slash}TKD4") (class "Default")
      (node (ref "IC1") (pin "10") (pinfunction "A_10") (pintype "input"))
      (node (ref "TKD4") (pin "2") (pinfunction "2_2") (pintype "passive"))
      (node (ref "U1") (pin "27") (pinfunction "(T0/OC4D/ADC10)PD7_27") (pintype "bidirectional"))
      (node (ref "U2") (pin "27") (pinfunction "(T0/OC4D/ADC10)PD7_27") (pintype "bidirectional"))
    )
    (net (code "20") (name "/DIO7{slash}RST_LCD") (class "Default")
      (node (ref "JP1") (pin "8") (pinfunction "8_8") (pintype "passive"))
      (node (ref "JP2") (pin "3") (pinfunction "3_3") (pintype "passive"))
      (node (ref "U1") (pin "1") (pinfunction "(INT6/AIN0)PE6_1") (pintype "bidirectional"))
      (node (ref "U2") (pin "1") (pinfunction "(INT6/AIN0)PE6_1") (pintype "bidirectional"))
    )
    (net (code "21") (name "/DIO8{slash}CARD_CS") (class "Default")
      (node (ref "JP1") (pin "6") (pinfunction "6_6") (pintype "passive"))
      (node (ref "JP2") (pin "5") (pinfunction "5_5") (pintype "passive"))
      (node (ref "U1") (pin "28") (pinfunction "(ADC11/PCINT4)PB4_28") (pintype "bidirectional"))
      (node (ref "U2") (pin "28") (pinfunction "(ADC11/PCINT4)PB4_28") (pintype "bidirectional"))
    )
    (net (code "22") (name "/DIO9{slash}LCD_CS") (class "Default")
      (node (ref "JP1") (pin "5") (pinfunction "5_5") (pintype "passive"))
      (node (ref "JP2") (pin "6") (pinfunction "6_6") (pintype "passive"))
      (node (ref "U1") (pin "29") (pinfunction "(PCINT5/OC1A/#OC4B/ADC12)PB5_29") (pintype "bidirectional"))
      (node (ref "U2") (pin "29") (pinfunction "(PCINT5/OC1A/#OC4B/ADC12)PB5_29") (pintype "bidirectional"))
    )
    (net (code "23") (name "/DIO10{slash}DC_LCD") (class "Default")
      (node (ref "JP1") (pin "7") (pinfunction "7_7") (pintype "passive"))
      (node (ref "JP2") (pin "4") (pinfunction "4_4") (pintype "passive"))
      (node (ref "U1") (pin "30") (pinfunction "(PCINT6/OC1B/OC4B/ADC13)PB6_30") (pintype "bidirectional"))
      (node (ref "U2") (pin "30") (pinfunction "(PCINT6/OC1B/OC4B/ADC13)PB6_30") (pintype "bidirectional"))
    )
    (net (code "24") (name "/DIO11") (class "Default")
      (node (ref "IC1") (pin "11") (pinfunction "B_11") (pintype "input"))
      (node (ref "U1") (pin "12") (pinfunction "(PCINT7/OC0A/OC1C/#RTS)PB7_12") (pintype "bidirectional"))
      (node (ref "U2") (pin "12") (pinfunction "(PCINT7/OC0A/OC1C/#RTS)PB7_12") (pintype "bidirectional"))
    )
    (net (code "25") (name "/DIO12{slash}TKD5") (class "Default")
      (node (ref "IC1") (pin "14") (pinfunction "C_14") (pintype "input"))
      (node (ref "TKD5") (pin "2") (pinfunction "2_2") (pintype "passive"))
      (node (ref "U1") (pin "26") (pinfunction "(T1/#OC4D/ADC9)PD6_26") (pintype "bidirectional"))
      (node (ref "U2") (pin "26") (pinfunction "(T1/#OC4D/ADC9)PD6_26") (pintype "bidirectional"))
    )
    (net (code "26") (name "/DIO13") (class "Default")
      (node (ref "IC1") (pin "13") (pinfunction "D_13") (pintype "input"))
      (node (ref "U1") (pin "32") (pinfunction "(ICP3/CLK0/OC4A)PC7_32") (pintype "bidirectional"))
      (node (ref "U2") (pin "32") (pinfunction "(ICP3/CLK0/OC4A)PC7_32") (pintype "bidirectional"))
    )
    (net (code "27") (name "/HWB") (class "Default")
      (node (ref "R6") (pin "2") (pinfunction "2_2") (pintype "passive"))
      (node (ref "U1") (pin "33") (pinfunction "(#HWB)PE2_33") (pintype "bidirectional"))
      (node (ref "U2") (pin "33") (pinfunction "(#HWB)PE2_33") (pintype "bidirectional"))
    )
    (net (code "28") (name "/I14") (class "Default")
      (node (ref "IC1") (pin "16") (pinfunction "X15_16") (pintype "input"))
    )
    (net (code "29") (name "/I15") (class "Default")
      (node (ref "IC1") (pin "17") (pinfunction "X14_17") (pintype "input"))
    )
    (net (code "30") (name "/I16") (class "Default")
      (node (ref "IC1") (pin "18") (pinfunction "X13_18") (pintype "input"))
    )
    (net (code "31") (name "/I17") (class "Default")
      (node (ref "IC1") (pin "19") (pinfunction "X12_19") (pintype "input"))
    )
    (net (code "32") (name "/I18") (class "Default")
      (node (ref "IC1") (pin "20") (pinfunction "X11_20") (pintype "input"))
    )
    (net (code "33") (name "/I19") (class "Default")
      (node (ref "IC1") (pin "21") (pinfunction "X10_21") (pintype "input"))
    )
    (net (code "34") (name "/MISO") (class "Default")
      (node (ref "J1") (pin "1") (pinfunction "1_1") (pintype "passive"))
      (node (ref "JP1") (pin "2") (pinfunction "2_2") (pintype "passive"))
      (node (ref "JP2") (pin "9") (pinfunction "9_9") (pintype "passive"))
      (node (ref "U1") (pin "11") (pinfunction "(PD0/MISO/PCINT3)PB3_11") (pintype "bidirectional"))
      (node (ref "U2") (pin "11") (pinfunction "(PD0/MISO/PCINT3)PB3_11") (pintype "bidirectional"))
    )
    (net (code "35") (name "/MOSI") (class "Default")
      (node (ref "J1") (pin "4") (pinfunction "4_4") (pintype "passive"))
      (node (ref "JP1") (pin "4") (pinfunction "4_4") (pintype "passive"))
      (node (ref "JP2") (pin "7") (pinfunction "7_7") (pintype "passive"))
      (node (ref "U1") (pin "10") (pinfunction "(PDI/MOSI/PCINT2)PB2_10") (pintype "bidirectional"))
      (node (ref "U2") (pin "10") (pinfunction "(PDI/MOSI/PCINT2)PB2_10") (pintype "bidirectional"))
    )
    (net (code "36") (name "/ON") (class "Default")
      (node (ref "JP3") (pin "4") (pinfunction "4_4") (pintype "passive"))
      (node (ref "RN3") (pin "7") (pinfunction "2_7") (pintype "passive"))
    )
    (net (code "37") (name "/Q1") (class "Default")
      (node (ref "C3") (pin "2") (pinfunction "2_2") (pintype "passive"))
      (node (ref "R5") (pin "2") (pinfunction "2_2") (pintype "passive"))
      (node (ref "U1") (pin "17") (pinfunction "XTAL1_17") (pintype "bidirectional"))
      (node (ref "U2") (pin "17") (pinfunction "XTAL1_17") (pintype "bidirectional"))
      (node (ref "X1") (pin "1") (pinfunction "C1_1") (pintype "passive"))
    )
    (net (code "38") (name "/Q2") (class "Default")
      (node (ref "C2") (pin "2") (pinfunction "2_2") (pintype "passive"))
      (node (ref "R5") (pin "1") (pinfunction "1_1") (pintype "passive"))
      (node (ref "U1") (pin "16") (pinfunction "XTAL2_16") (pintype "bidirectional"))
      (node (ref "U2") (pin "16") (pinfunction "XTAL2_16") (pintype "bidirectional"))
      (node (ref "X1") (pin "3") (pinfunction "C2_3") (pintype "passive"))
    )
    (net (code "39") (name "/RESET") (class "Default")
      (node (ref "D1") (pin "A") (pinfunction "A_A") (pintype "passive"))
      (node (ref "J1") (pin "5") (pinfunction "5_5") (pintype "passive"))
      (node (ref "R3") (pin "2") (pinfunction "2_2") (pintype "passive"))
      (node (ref "S8") (pin "1") (pinfunction "1_1") (pintype "passive"))
      (node (ref "S8") (pin "2") (pinfunction "2_2") (pintype "passive"))
      (node (ref "U1") (pin "13") (pinfunction "RESET_13") (pintype "input"))
      (node (ref "U2") (pin "13") (pinfunction "RESET_13") (pintype "input"))
    )
    (net (code "40") (name "/RX") (class "Default")
      (node (ref "JP3") (pin "3") (pinfunction "3_3") (pintype "passive"))
      (node (ref "U1") (pin "20") (pinfunction "(RXD1/AIN1/INT2)PD2_20") (pintype "bidirectional"))
      (node (ref "U2") (pin "20") (pinfunction "(RXD1/AIN1/INT2)PD2_20") (pintype "bidirectional"))
    )
    (net (code "41") (name "/RX_LED") (class "Default")
      (node (ref "LED") (pin "C") (pinfunction "C_C") (pintype "passive"))
      (node (ref "U1") (pin "8") (pinfunction "(SS/PCINT0)PB0_8") (pintype "bidirectional"))
      (node (ref "U2") (pin "8") (pinfunction "(SS/PCINT0)PB0_8") (pintype "bidirectional"))
    )
    (net (code "42") (name "/SCK") (class "Default")
      (node (ref "J1") (pin "3") (pinfunction "3_3") (pintype "passive"))
      (node (ref "JP1") (pin "3") (pinfunction "3_3") (pintype "passive"))
      (node (ref "JP2") (pin "8") (pinfunction "8_8") (pintype "passive"))
      (node (ref "U1") (pin "9") (pinfunction "(SCLK/PCINT1)PB1_9") (pintype "bidirectional"))
      (node (ref "U2") (pin "9") (pinfunction "(SCLK/PCINT1)PB1_9") (pintype "bidirectional"))
    )
    (net (code "43") (name "/SCL") (class "Default")
      (node (ref "I2C01") (pin "4") (pinfunction "4_4") (pintype "passive"))
      (node (ref "I2C02") (pin "4") (pinfunction "4_4") (pintype "passive"))
      (node (ref "I2C03") (pin "4") (pinfunction "4_4") (pintype "passive"))
      (node (ref "R10") (pin "2") (pinfunction "2_2") (pintype "passive"))
      (node (ref "R101") (pin "1") (pinfunction "1_1") (pintype "passive"))
      (node (ref "U1") (pin "18") (pinfunction "(OC0B/SCL/INT0)PD0_18") (pintype "bidirectional"))
      (node (ref "U2") (pin "18") (pinfunction "(OC0B/SCL/INT0)PD0_18") (pintype "bidirectional"))
      (node (ref "U3") (pin "6") (pinfunction "SCL_6") (pintype "input"))
      (node (ref "U4") (pin "1") (pinfunction "SCL_1") (pintype "bidirectional"))
    )
    (net (code "44") (name "/SDA") (class "Default")
      (node (ref "I2C01") (pin "3") (pinfunction "3_3") (pintype "passive"))
      (node (ref "I2C02") (pin "3") (pinfunction "3_3") (pintype "passive"))
      (node (ref "I2C03") (pin "3") (pinfunction "3_3") (pintype "passive"))
      (node (ref "R102") (pin "1") (pinfunction "1_1") (pintype "passive"))
      (node (ref "R9") (pin "1") (pinfunction "1_1") (pintype "passive"))
      (node (ref "U1") (pin "19") (pinfunction "(SDA/INT1)PD1_19") (pintype "bidirectional"))
      (node (ref "U2") (pin "19") (pinfunction "(SDA/INT1)PD1_19") (pintype "bidirectional"))
      (node (ref "U3") (pin "5") (pinfunction "SDA_5") (pintype "bidirectional"))
      (node (ref "U4") (pin "16") (pinfunction "SDA_16") (pintype "bidirectional"))
    )
    (net (code "45") (name "/TX") (class "Default")
      (node (ref "JP3") (pin "1") (pinfunction "1_1") (pintype "passive"))
      (node (ref "U1") (pin "21") (pinfunction "(TXD1/INT3)PD3_21") (pintype "bidirectional"))
      (node (ref "U2") (pin "21") (pinfunction "(TXD1/INT3)PD3_21") (pintype "bidirectional"))
    )
    (net (code "46") (name "/TX_LED") (class "Default")
      (node (ref "TX") (pin "C") (pinfunction "C_C") (pintype "passive"))
      (node (ref "U1") (pin "22") (pinfunction "(XCK1/#CTS)PD5_22") (pintype "bidirectional"))
      (node (ref "U2") (pin "22") (pinfunction "(XCK1/#CTS)PD5_22") (pintype "bidirectional"))
    )
    (net (code "47") (name "/UCAP") (class "Default")
      (node (ref "C5") (pin "1") (pinfunction "1_1") (pintype "passive"))
      (node (ref "U1") (pin "6") (pinfunction "UCAP_6") (pintype "passive"))
      (node (ref "U2") (pin "6") (pinfunction "UCAP_6") (pintype "passive"))
    )
    (net (code "48") (name "/VP1") (class "Default")
      (node (ref "PTZ3") (pin "P$42") (pinfunction "1_P$42") (pintype "power_in"))
      (node (ref "SJ1") (pin "2") (pinfunction "2_2") (pintype "passive"))
    )
    (net (code "49") (name "/VP2") (class "Default")
      (node (ref "PTZ4") (pin "P$42") (pinfunction "1_P$42") (pintype "power_in"))
      (node (ref "SJ2") (pin "2") (pinfunction "2_2") (pintype "passive"))
    )
    (net (code "50") (name "/VP3") (class "Default")
      (node (ref "PTZ1") (pin "P$42") (pinfunction "1_P$42") (pintype "power_in"))
      (node (ref "SJ3") (pin "2") (pinfunction "2_2") (pintype "passive"))
    )
    (net (code "51") (name "/VP4") (class "Default")
      (node (ref "PTZ2") (pin "P$42") (pinfunction "1_P$42") (pintype "power_in"))
      (node (ref "SJ4") (pin "2") (pinfunction "2_2") (pintype "passive"))
    )
    (net (code "52") (name "/VUSB") (class "Default")
      (node (ref "C7") (pin "+") (pinfunction "+_+") (pintype "passive"))
      (node (ref "C8") (pin "+") (pinfunction "+_+") (pintype "passive"))
      (node (ref "C9") (pin "1") (pinfunction "1_1") (pintype "passive"))
      (node (ref "F1") (pin "2") (pinfunction "2_2") (pintype "passive"))
      (node (ref "JP3") (pin "7") (pinfunction "7_7") (pintype "passive"))
      (node (ref "JP3") (pin "8") (pinfunction "8_8") (pintype "passive"))
      (node (ref "SJ5") (pin "1") (pinfunction "1_1") (pintype "passive"))
      (node (ref "U1") (pin "7") (pinfunction "VBUS_7") (pintype "input"))
      (node (ref "U2") (pin "7") (pinfunction "VBUS_7") (pintype "input"))
    )
    (net (code "53") (name "/X0") (class "Default")
      (node (ref "IC1") (pin "9") (pinfunction "X0_9") (pintype "input"))
      (node (ref "J16") (pin "1") (pinfunction "1_1") (pintype "bidirectional"))
      (node (ref "S0") (pin "1") (pinfunction "1_1") (pintype "passive"))
      (node (ref "TK0") (pin "2") (pinfunction "2_2") (pintype "passive"))
    )
    (net (code "54") (name "/X1") (class "Default")
      (node (ref "IC1") (pin "8") (pinfunction "X1_8") (pintype "input"))
      (node (ref "J2") (pin "1") (pinfunction "1_1") (pintype "bidirectional"))
      (node (ref "S1") (pin "1") (pinfunction "1_1") (pintype "passive"))
      (node (ref "TK1") (pin "2") (pinfunction "2_2") (pintype "passive"))
    )
    (net (code "55") (name "/X2") (class "Default")
      (node (ref "IC1") (pin "7") (pinfunction "X2_7") (pintype "input"))
      (node (ref "J3") (pin "1") (pinfunction "1_1") (pintype "bidirectional"))
      (node (ref "S2") (pin "1") (pinfunction "1_1") (pintype "passive"))
      (node (ref "TK2") (pin "2") (pinfunction "2_2") (pintype "passive"))
    )
    (net (code "56") (name "/X3") (class "Default")
      (node (ref "IC1") (pin "6") (pinfunction "X3_6") (pintype "input"))
      (node (ref "J7") (pin "1") (pinfunction "1_1") (pintype "bidirectional"))
      (node (ref "S3") (pin "1") (pinfunction "1_1") (pintype "passive"))
      (node (ref "TK3") (pin "2") (pinfunction "2_2") (pintype "passive"))
    )
    (net (code "57") (name "/X4") (class "Default")
      (node (ref "IC1") (pin "5") (pinfunction "X4_5") (pintype "input"))
      (node (ref "J13") (pin "1") (pinfunction "1_1") (pintype "bidirectional"))
      (node (ref "S4") (pin "1") (pinfunction "1_1") (pintype "passive"))
      (node (ref "TK4") (pin "2") (pinfunction "2_2") (pintype "passive"))
    )
    (net (code "58") (name "/X5") (class "Default")
      (node (ref "IC1") (pin "4") (pinfunction "X5_4") (pintype "input"))
      (node (ref "J4") (pin "1") (pinfunction "1_1") (pintype "bidirectional"))
      (node (ref "S5") (pin "1") (pinfunction "1_1") (pintype "passive"))
      (node (ref "TK5") (pin "2") (pinfunction "2_2") (pintype "passive"))
    )
    (net (code "59") (name "/X6") (class "Default")
      (node (ref "IC1") (pin "3") (pinfunction "X6_3") (pintype "input"))
      (node (ref "J5") (pin "1") (pinfunction "1_1") (pintype "bidirectional"))
      (node (ref "S6") (pin "1") (pinfunction "1_1") (pintype "passive"))
      (node (ref "TK6") (pin "2") (pinfunction "2_2") (pintype "passive"))
    )
    (net (code "60") (name "/X7") (class "Default")
      (node (ref "IC1") (pin "2") (pinfunction "X7_2") (pintype "input"))
      (node (ref "J6") (pin "1") (pinfunction "1_1") (pintype "bidirectional"))
      (node (ref "S7") (pin "1") (pinfunction "1_1") (pintype "passive"))
      (node (ref "TK7") (pin "2") (pinfunction "2_2") (pintype "passive"))
    )
    (net (code "61") (name "/XUSB") (class "Default")
      (node (ref "F1") (pin "1") (pinfunction "1_1") (pintype "passive"))
      (node (ref "X2") (pin "1") (pinfunction "1_1") (pintype "bidirectional"))
    )
    (net (code "62") (name "AGND") (class "Default")
      (node (ref "C1") (pin "1") (pinfunction "1_1") (pintype "passive"))
      (node (ref "NM2") (pin "1") (pinfunction "1_1") (pintype "passive"))
      (node (ref "U1") (pin "43") (pinfunction "GND3_43") (pintype "power_in"))
      (node (ref "U2") (pin "43") (pinfunction "GND3_43") (pintype "power_in"))
    )
    (net (code "63") (name "GND") (class "Default")
      (node (ref "C10") (pin "-") (pinfunction "-_-") (pintype "passive"))
      (node (ref "C11") (pin "2") (pinfunction "2_2") (pintype "passive"))
      (node (ref "C12") (pin "2") (pinfunction "2_2") (pintype "passive"))
      (node (ref "C13") (pin "2") (pinfunction "2_2") (pintype "passive"))
      (node (ref "C14") (pin "2") (pinfunction "2_2") (pintype "passive"))
      (node (ref "C15") (pin "2") (pinfunction "2_2") (pintype "passive"))
      (node (ref "C17") (pin "2") (pinfunction "2_2") (pintype "passive"))
      (node (ref "C18") (pin "2") (pinfunction "2_2") (pintype "passive"))
      (node (ref "C19") (pin "2") (pinfunction "2_2") (pintype "passive"))
      (node (ref "C2") (pin "1") (pinfunction "1_1") (pintype "passive"))
      (node (ref "C3") (pin "1") (pinfunction "1_1") (pintype "passive"))
      (node (ref "C4") (pin "2") (pinfunction "2_2") (pintype "passive"))
      (node (ref "C6") (pin "2") (pinfunction "2_2") (pintype "passive"))
      (node (ref "C7") (pin "-") (pinfunction "-_-") (pintype "passive"))
      (node (ref "C8") (pin "-") (pinfunction "-_-") (pintype "passive"))
      (node (ref "C9") (pin "2") (pinfunction "2_2") (pintype "passive"))
      (node (ref "H1") (pin "P$1") (pinfunction "PAD_P$1") (pintype "bidirectional"))
      (node (ref "H2") (pin "P$1") (pinfunction "PAD_P$1") (pintype "bidirectional"))
      (node (ref "H3") (pin "P$1") (pinfunction "PAD_P$1") (pintype "bidirectional"))
      (node (ref "H4") (pin "P$1") (pinfunction "PAD_P$1") (pintype "bidirectional"))
      (node (ref "H5") (pin "P$1") (pinfunction "PAD_P$1") (pintype "bidirectional"))
      (node (ref "H6") (pin "P$1") (pinfunction "PAD_P$1") (pintype "bidirectional"))
      (node (ref "H7") (pin "P$1") (pinfunction "PAD_P$1") (pintype "bidirectional"))
      (node (ref "H8") (pin "P$1") (pinfunction "PAD_P$1") (pintype "bidirectional"))
      (node (ref "I2C01") (pin "1") (pinfunction "1_1") (pintype "passive"))
      (node (ref "I2C02") (pin "1") (pinfunction "1_1") (pintype "passive"))
      (node (ref "I2C03") (pin "1") (pinfunction "1_1") (pintype "passive"))
      (node (ref "IC1") (pin "12") (pinfunction "VSS_12") (pintype "power_in"))
      (node (ref "IC1") (pin "15") (pinfunction "INH_15") (pintype "input"))
      (node (ref "J1") (pin "6") (pinfunction "6_6") (pintype "passive"))
      (node (ref "J10") (pin "4") (pinfunction "4_4") (pintype "bidirectional"))
      (node (ref "J12") (pin "4") (pinfunction "4_4") (pintype "bidirectional"))
      (node (ref "J13") (pin "4") (pinfunction "4_4") (pintype "bidirectional"))
      (node (ref "J16") (pin "4") (pinfunction "4_4") (pintype "bidirectional"))
      (node (ref "J2") (pin "4") (pinfunction "4_4") (pintype "bidirectional"))
      (node (ref "J3") (pin "4") (pinfunction "4_4") (pintype "bidirectional"))
      (node (ref "J4") (pin "4") (pinfunction "4_4") (pintype "bidirectional"))
      (node (ref "J5") (pin "4") (pinfunction "4_4") (pintype "bidirectional"))
      (node (ref "J6") (pin "4") (pinfunction "4_4") (pintype "bidirectional"))
      (node (ref "J7") (pin "4") (pinfunction "4_4") (pintype "bidirectional"))
      (node (ref "J8") (pin "4") (pinfunction "4_4") (pintype "bidirectional"))
      (node (ref "J9") (pin "4") (pinfunction "4_4") (pintype "bidirectional"))
      (node (ref "JP1") (pin "10") (pinfunction "10_10") (pintype "passive"))
      (node (ref "JP2") (pin "1") (pinfunction "1_1") (pintype "passive"))
      (node (ref "JP3") (pin "5") (pinfunction "5_5") (pintype "passive"))
      (node (ref "NM1") (pin "1") (pinfunction "1_1") (pintype "passive"))
      (node (ref "NM2") (pin "2") (pinfunction "2_2") (pintype "passive"))
      (node (ref "P1") (pin "A") (pinfunction "A_A") (pintype "passive"))
      (node (ref "PTZ1") (pin "P$52") (pinfunction "2_P$52") (pintype "power_in"))
      (node (ref "PTZ2") (pin "P$52") (pinfunction "2_P$52") (pintype "power_in"))
      (node (ref "PTZ3") (pin "P$52") (pinfunction "2_P$52") (pintype "power_in"))
      (node (ref "PTZ4") (pin "P$52") (pinfunction "2_P$52") (pintype "power_in"))
      (node (ref "PWR") (pin "C") (pinfunction "C_C") (pintype "passive"))
      (node (ref "R6") (pin "1") (pinfunction "1_1") (pintype "passive"))
      (node (ref "RN3") (pin "5") (pinfunction "2_5") (pintype "passive"))
      (node (ref "RN3") (pin "8") (pinfunction "2_8") (pintype "passive"))
      (node (ref "S0") (pin "2") (pinfunction "2_2") (pintype "passive"))
      (node (ref "S1") (pin "2") (pinfunction "2_2") (pintype "passive"))
      (node (ref "S10") (pin "P$1") (pinfunction "1_P$1") (pintype "passive"))
      (node (ref "S10") (pin "P$2") (pinfunction "2_P$2") (pintype "passive"))
      (node (ref "S11") (pin "P$3") (pinfunction "3_P$3") (pintype "passive"))
      (node (ref "S11") (pin "P$4") (pinfunction "4_P$4") (pintype "passive"))
      (node (ref "S12") (pin "P$1") (pinfunction "1_P$1") (pintype "passive"))
      (node (ref "S12") (pin "P$2") (pinfunction "2_P$2") (pintype "passive"))
      (node (ref "S13") (pin "P$1") (pinfunction "1_P$1") (pintype "passive"))
      (node (ref "S13") (pin "P$2") (pinfunction "2_P$2") (pintype "passive"))
      (node (ref "S14") (pin "P$1") (pinfunction "1_P$1") (pintype "passive"))
      (node (ref "S14") (pin "P$2") (pinfunction "2_P$2") (pintype "passive"))
      (node (ref "S2") (pin "2") (pinfunction "2_2") (pintype "passive"))
      (node (ref "S3") (pin "2") (pinfunction "2_2") (pintype "passive"))
      (node (ref "S4") (pin "2") (pinfunction "2_2") (pintype "passive"))
      (node (ref "S5") (pin "2") (pinfunction "2_2") (pintype "passive"))
      (node (ref "S6") (pin "2") (pinfunction "2_2") (pintype "passive"))
      (node (ref "S7") (pin "2") (pinfunction "2_2") (pintype "passive"))
      (node (ref "S8") (pin "3") (pinfunction "3_3") (pintype "passive"))
      (node (ref "S8") (pin "4") (pinfunction "4_4") (pintype "passive"))
      (node (ref "T1") (pin "2") (pinfunction "E_2") (pintype "passive"))
      (node (ref "TK0") (pin "1") (pinfunction "1_1") (pintype "passive"))
      (node (ref "TK1") (pin "1") (pinfunction "1_1") (pintype "passive"))
      (node (ref "TK2") (pin "1") (pinfunction "1_1") (pintype "passive"))
      (node (ref "TK3") (pin "1") (pinfunction "1_1") (pintype "passive"))
      (node (ref "TK4") (pin "1") (pinfunction "1_1") (pintype "passive"))
      (node (ref "TK5") (pin "1") (pinfunction "1_1") (pintype "passive"))
      (node (ref "TK6") (pin "1") (pinfunction "1_1") (pintype "passive"))
      (node (ref "TK7") (pin "1") (pinfunction "1_1") (pintype "passive"))
      (node (ref "TKD0") (pin "1") (pinfunction "1_1") (pintype "passive"))
      (node (ref "TKD1") (pin "1") (pinfunction "1_1") (pintype "passive"))
      (node (ref "TKD2") (pin "1") (pinfunction "1_1") (pintype "passive"))
      (node (ref "TKD3") (pin "1") (pinfunction "1_1") (pintype "passive"))
      (node (ref "TKD4") (pin "1") (pinfunction "1_1") (pintype "passive"))
      (node (ref "TKD5") (pin "1") (pinfunction "1_1") (pintype "passive"))
      (node (ref "U1") (pin "15") (pinfunction "GND_15") (pintype "power_in"))
      (node (ref "U1") (pin "23") (pinfunction "GND1_23") (pintype "power_in"))
      (node (ref "U1") (pin "35") (pinfunction "GND2_35") (pintype "power_in"))
      (node (ref "U1") (pin "P$1") (pinfunction "PAD_P$1") (pintype "power_in"))
      (node (ref "U2") (pin "15") (pinfunction "GND_15") (pintype "power_in"))
      (node (ref "U2") (pin "23") (pinfunction "GND1_23") (pintype "power_in"))
      (node (ref "U2") (pin "35") (pinfunction "GND2_35") (pintype "power_in"))
      (node (ref "U2") (pin "EXP") (pinfunction "PAD_EXP") (pintype "power_in"))
      (node (ref "U3") (pin "1") (pinfunction "A0_1") (pintype "input"))
      (node (ref "U3") (pin "2") (pinfunction "A1_2") (pintype "input"))
      (node (ref "U3") (pin "3") (pinfunction "A2_3") (pintype "input"))
      (node (ref "U3") (pin "4") (pinfunction "GND_4") (pintype "passive"))
      (node (ref "U3") (pin "7") (pinfunction "WP_7") (pintype "input"))
      (node (ref "U4") (pin "11") (pinfunction "GND_11") (pintype "bidirectional"))
      (node (ref "U4") (pin "9") (pinfunction "GND_9") (pintype "bidirectional"))
      (node (ref "US0") (pin "3") (pinfunction "3_3") (pintype "passive"))
      (node (ref "US0") (pin "4") (pinfunction "4_4") (pintype "passive"))
      (node (ref "US1") (pin "3") (pinfunction "3_3") (pintype "passive"))
      (node (ref "US1") (pin "4") (pinfunction "4_4") (pintype "passive"))
      (node (ref "US2") (pin "3") (pinfunction "3_3") (pintype "passive"))
      (node (ref "US2") (pin "4") (pinfunction "4_4") (pintype "passive"))
      (node (ref "US3") (pin "3") (pinfunction "3_3") (pintype "passive"))
      (node (ref "US3") (pin "4") (pinfunction "4_4") (pintype "passive"))
      (node (ref "X1") (pin "2") (pinfunction "GND_2") (pintype "passive"))
      (node (ref "X1") (pin "4") (pinfunction "GND_4") (pintype "passive"))
    )
    (net (code "64") (name "Net-(L4-Pad1)") (class "Default")
      (node (ref "L4") (pin "1") (pinfunction "1_1") (pintype "passive"))
      (node (ref "R7") (pin "2") (pinfunction "2_2") (pintype "passive"))
      (node (ref "R8") (pin "2") (pinfunction "2_2") (pintype "passive"))
      (node (ref "X2") (pin "P$1") (pinfunction "P$1_P$1") (pintype "bidirectional"))
      (node (ref "X2") (pin "P$2") (pinfunction "P$2_P$2") (pintype "bidirectional"))
    )
    (net (code "65") (name "Net-(PWR-PadA)") (class "Default")
      (node (ref "PWR") (pin "A") (pinfunction "A_A") (pintype "passive"))
      (node (ref "RN2") (pin "1") (pinfunction "1_1") (pintype "passive"))
    )
    (net (code "66") (name "Net-(RN1A-2)") (class "Default")
      (node (ref "R8") (pin "1") (pinfunction "1_1") (pintype "passive"))
      (node (ref "RN1") (pin "8") (pinfunction "2_8") (pintype "passive"))
      (node (ref "X2") (pin "2") (pinfunction "2_2") (pintype "bidirectional"))
    )
    (net (code "67") (name "Net-(RN1D-2)") (class "Default")
      (node (ref "R7") (pin "1") (pinfunction "1_1") (pintype "passive"))
      (node (ref "RN1") (pin "5") (pinfunction "2_5") (pintype "passive"))
      (node (ref "X2") (pin "3") (pinfunction "3_3") (pintype "bidirectional"))
    )
    (net (code "68") (name "Net-(RN2C-1)") (class "Default")
      (node (ref "LED") (pin "A") (pinfunction "A_A") (pintype "passive"))
      (node (ref "RN2") (pin "3") (pinfunction "1_3") (pintype "passive"))
    )
    (net (code "69") (name "Net-(RN2D-1)") (class "Default")
      (node (ref "RN2") (pin "4") (pinfunction "1_4") (pintype "passive"))
      (node (ref "TX") (pin "A") (pinfunction "A_A") (pintype "passive"))
    )
    (net (code "70") (name "Net-(R_S3-Pad2)") (class "Default")
      (node (ref "R_S3") (pin "2") (pinfunction "2_2") (pintype "passive"))
      (node (ref "R_S6") (pin "1") (pinfunction "1_1") (pintype "passive"))
    )
    (net (code "71") (name "Net-(S11-1)") (class "Default")
      (node (ref "R_S2") (pin "1") (pinfunction "1_1") (pintype "passive"))
      (node (ref "R_S6") (pin "2") (pinfunction "2_2") (pintype "passive"))
      (node (ref "S11") (pin "P$1") (pinfunction "1_P$1") (pintype "passive"))
      (node (ref "S11") (pin "P$2") (pinfunction "2_P$2") (pintype "passive"))
    )
    (net (code "72") (name "Net-(S12-3)") (class "Default")
      (node (ref "R_S3") (pin "1") (pinfunction "1_1") (pintype "passive"))
      (node (ref "R_S4") (pin "2") (pinfunction "2_2") (pintype "passive"))
      (node (ref "S12") (pin "P$3") (pinfunction "3_P$3") (pintype "passive"))
      (node (ref "S12") (pin "P$4") (pinfunction "4_P$4") (pintype "passive"))
    )
    (net (code "73") (name "Net-(S13-3)") (class "Default")
      (node (ref "R_S4") (pin "1") (pinfunction "1_1") (pintype "passive"))
      (node (ref "R_S5") (pin "2") (pinfunction "2_2") (pintype "passive"))
      (node (ref "S13") (pin "P$3") (pinfunction "3_P$3") (pintype "passive"))
      (node (ref "S13") (pin "P$4") (pinfunction "4_P$4") (pintype "passive"))
    )
    (net (code "74") (name "Net-(S14-3)") (class "Default")
      (node (ref "R_S5") (pin "1") (pinfunction "1_1") (pintype "passive"))
      (node (ref "S14") (pin "P$3") (pinfunction "3_P$3") (pintype "passive"))
      (node (ref "S14") (pin "P$4") (pinfunction "4_P$4") (pintype "passive"))
    )
    (net (code "75") (name "Net-(SG1-2)") (class "Default")
      (node (ref "SG1") (pin "-") (pinfunction "2_-") (pintype "passive"))
      (node (ref "T1") (pin "3") (pinfunction "C_3") (pintype "passive"))
    )
    (net (code "76") (name "Net-(T1-B)") (class "Default")
      (node (ref "R4") (pin "1") (pinfunction "1_1") (pintype "passive"))
      (node (ref "T1") (pin "1") (pinfunction "B_1") (pintype "passive"))
    )
    (net (code "77") (name "Net-(U4-C1)") (class "Default")
      (node (ref "C15") (pin "1") (pinfunction "1_1") (pintype "passive"))
      (node (ref "U4") (pin "10") (pinfunction "C1_10") (pintype "bidirectional"))
    )
    (net (code "78") (name "Net-(U4-SETC)") (class "Default")
      (node (ref "C16") (pin "2") (pinfunction "2_2") (pintype "passive"))
      (node (ref "U4") (pin "12") (pinfunction "SETC_12") (pintype "bidirectional"))
    )
    (net (code "79") (name "Net-(U4-SETP)") (class "Default")
      (node (ref "C16") (pin "1") (pinfunction "1_1") (pintype "passive"))
      (node (ref "U4") (pin "8") (pinfunction "SETP_8") (pintype "bidirectional"))
    )
    (net (code "80") (name "UGND") (class "Default")
      (node (ref "C5") (pin "2") (pinfunction "2_2") (pintype "passive"))
      (node (ref "L4") (pin "2") (pinfunction "2_2") (pintype "passive"))
      (node (ref "NM1") (pin "2") (pinfunction "2_2") (pintype "passive"))
      (node (ref "U1") (pin "5") (pinfunction "UGND_5") (pintype "power_in"))
      (node (ref "U2") (pin "5") (pinfunction "UGND_5") (pintype "power_in"))
      (node (ref "X2") (pin "4") (pinfunction "4_4") (pintype "bidirectional"))
    )
    (net (code "81") (name "unconnected-(J2-Pad2)") (class "Default")
      (node (ref "J2") (pin "2") (pinfunction "2_2") (pintype "bidirectional"))
    )
    (net (code "82") (name "unconnected-(J3-Pad2)") (class "Default")
      (node (ref "J3") (pin "2") (pinfunction "2_2") (pintype "bidirectional"))
    )
    (net (code "83") (name "unconnected-(J4-Pad2)") (class "Default")
      (node (ref "J4") (pin "2") (pinfunction "2_2") (pintype "bidirectional"))
    )
    (net (code "84") (name "unconnected-(J5-Pad2)") (class "Default")
      (node (ref "J5") (pin "2") (pinfunction "2_2") (pintype "bidirectional"))
    )
    (net (code "85") (name "unconnected-(J6-Pad2)") (class "Default")
      (node (ref "J6") (pin "2") (pinfunction "2_2") (pintype "bidirectional"))
    )
    (net (code "86") (name "unconnected-(J7-Pad2)") (class "Default")
      (node (ref "J7") (pin "2") (pinfunction "2_2") (pintype "bidirectional"))
    )
    (net (code "87") (name "unconnected-(J8-Pad2)") (class "Default")
      (node (ref "J8") (pin "2") (pinfunction "2_2") (pintype "bidirectional"))
    )
    (net (code "88") (name "unconnected-(J9-Pad2)") (class "Default")
      (node (ref "J9") (pin "2") (pinfunction "2_2") (pintype "bidirectional"))
    )
    (net (code "89") (name "unconnected-(J10-Pad2)") (class "Default")
      (node (ref "J10") (pin "2") (pinfunction "2_2") (pintype "bidirectional"))
    )
    (net (code "90") (name "unconnected-(J12-Pad2)") (class "Default")
      (node (ref "J12") (pin "2") (pinfunction "2_2") (pintype "bidirectional"))
    )
    (net (code "91") (name "unconnected-(J13-Pad2)") (class "Default")
      (node (ref "J13") (pin "2") (pinfunction "2_2") (pintype "bidirectional"))
    )
    (net (code "92") (name "unconnected-(J16-Pad2)") (class "Default")
      (node (ref "J16") (pin "2") (pinfunction "2_2") (pintype "bidirectional"))
    )
    (net (code "93") (name "unconnected-(RN1B-1-Pad2)") (class "Default")
      (node (ref "RN1") (pin "2") (pinfunction "1_2") (pintype "passive"))
    )
    (net (code "94") (name "unconnected-(RN1B-2-Pad7)") (class "Default")
      (node (ref "RN1") (pin "7") (pinfunction "2_7") (pintype "passive"))
    )
    (net (code "95") (name "unconnected-(RN1C-1-Pad3)") (class "Default")
      (node (ref "RN1") (pin "3") (pinfunction "1_3") (pintype "passive"))
    )
    (net (code "96") (name "unconnected-(RN1C-2-Pad6)") (class "Default")
      (node (ref "RN1") (pin "6") (pinfunction "2_6") (pintype "passive"))
    )
    (net (code "97") (name "unconnected-(RN2B-1-Pad2)") (class "Default")
      (node (ref "RN2") (pin "2") (pinfunction "1_2") (pintype "passive"))
    )
    (net (code "98") (name "unconnected-(RN2B-2-Pad7)") (class "Default")
      (node (ref "RN2") (pin "7") (pinfunction "2_7") (pintype "passive"))
    )
    (net (code "99") (name "unconnected-(U4-DRDY-Pad15)") (class "Default")
      (node (ref "U4") (pin "15") (pinfunction "DRDY_15") (pintype "bidirectional"))
    )
    (net (code "100") (name "unconnected-(U4-NC-Pad3)") (class "Default")
      (node (ref "U4") (pin "3") (pinfunction "NC_3") (pintype "bidirectional"))
    )
    (net (code "101") (name "unconnected-(U4-NC-Pad5)") (class "Default")
      (node (ref "U4") (pin "5") (pinfunction "NC_5") (pintype "bidirectional"))
    )
    (net (code "102") (name "unconnected-(U4-NC-Pad6)") (class "Default")
      (node (ref "U4") (pin "6") (pinfunction "NC_6") (pintype "bidirectional"))
    )
    (net (code "103") (name "unconnected-(U4-NC-Pad7)") (class "Default")
      (node (ref "U4") (pin "7") (pinfunction "NC_7") (pintype "bidirectional"))
    )
    (net (code "104") (name "unconnected-(U4-NC-Pad14)") (class "Default")
      (node (ref "U4") (pin "14") (pinfunction "NC_14") (pintype "bidirectional"))
    )
  )
)
